# PDU_Sch.net
KiCad netlist of a schematic drawn in Altium Designer
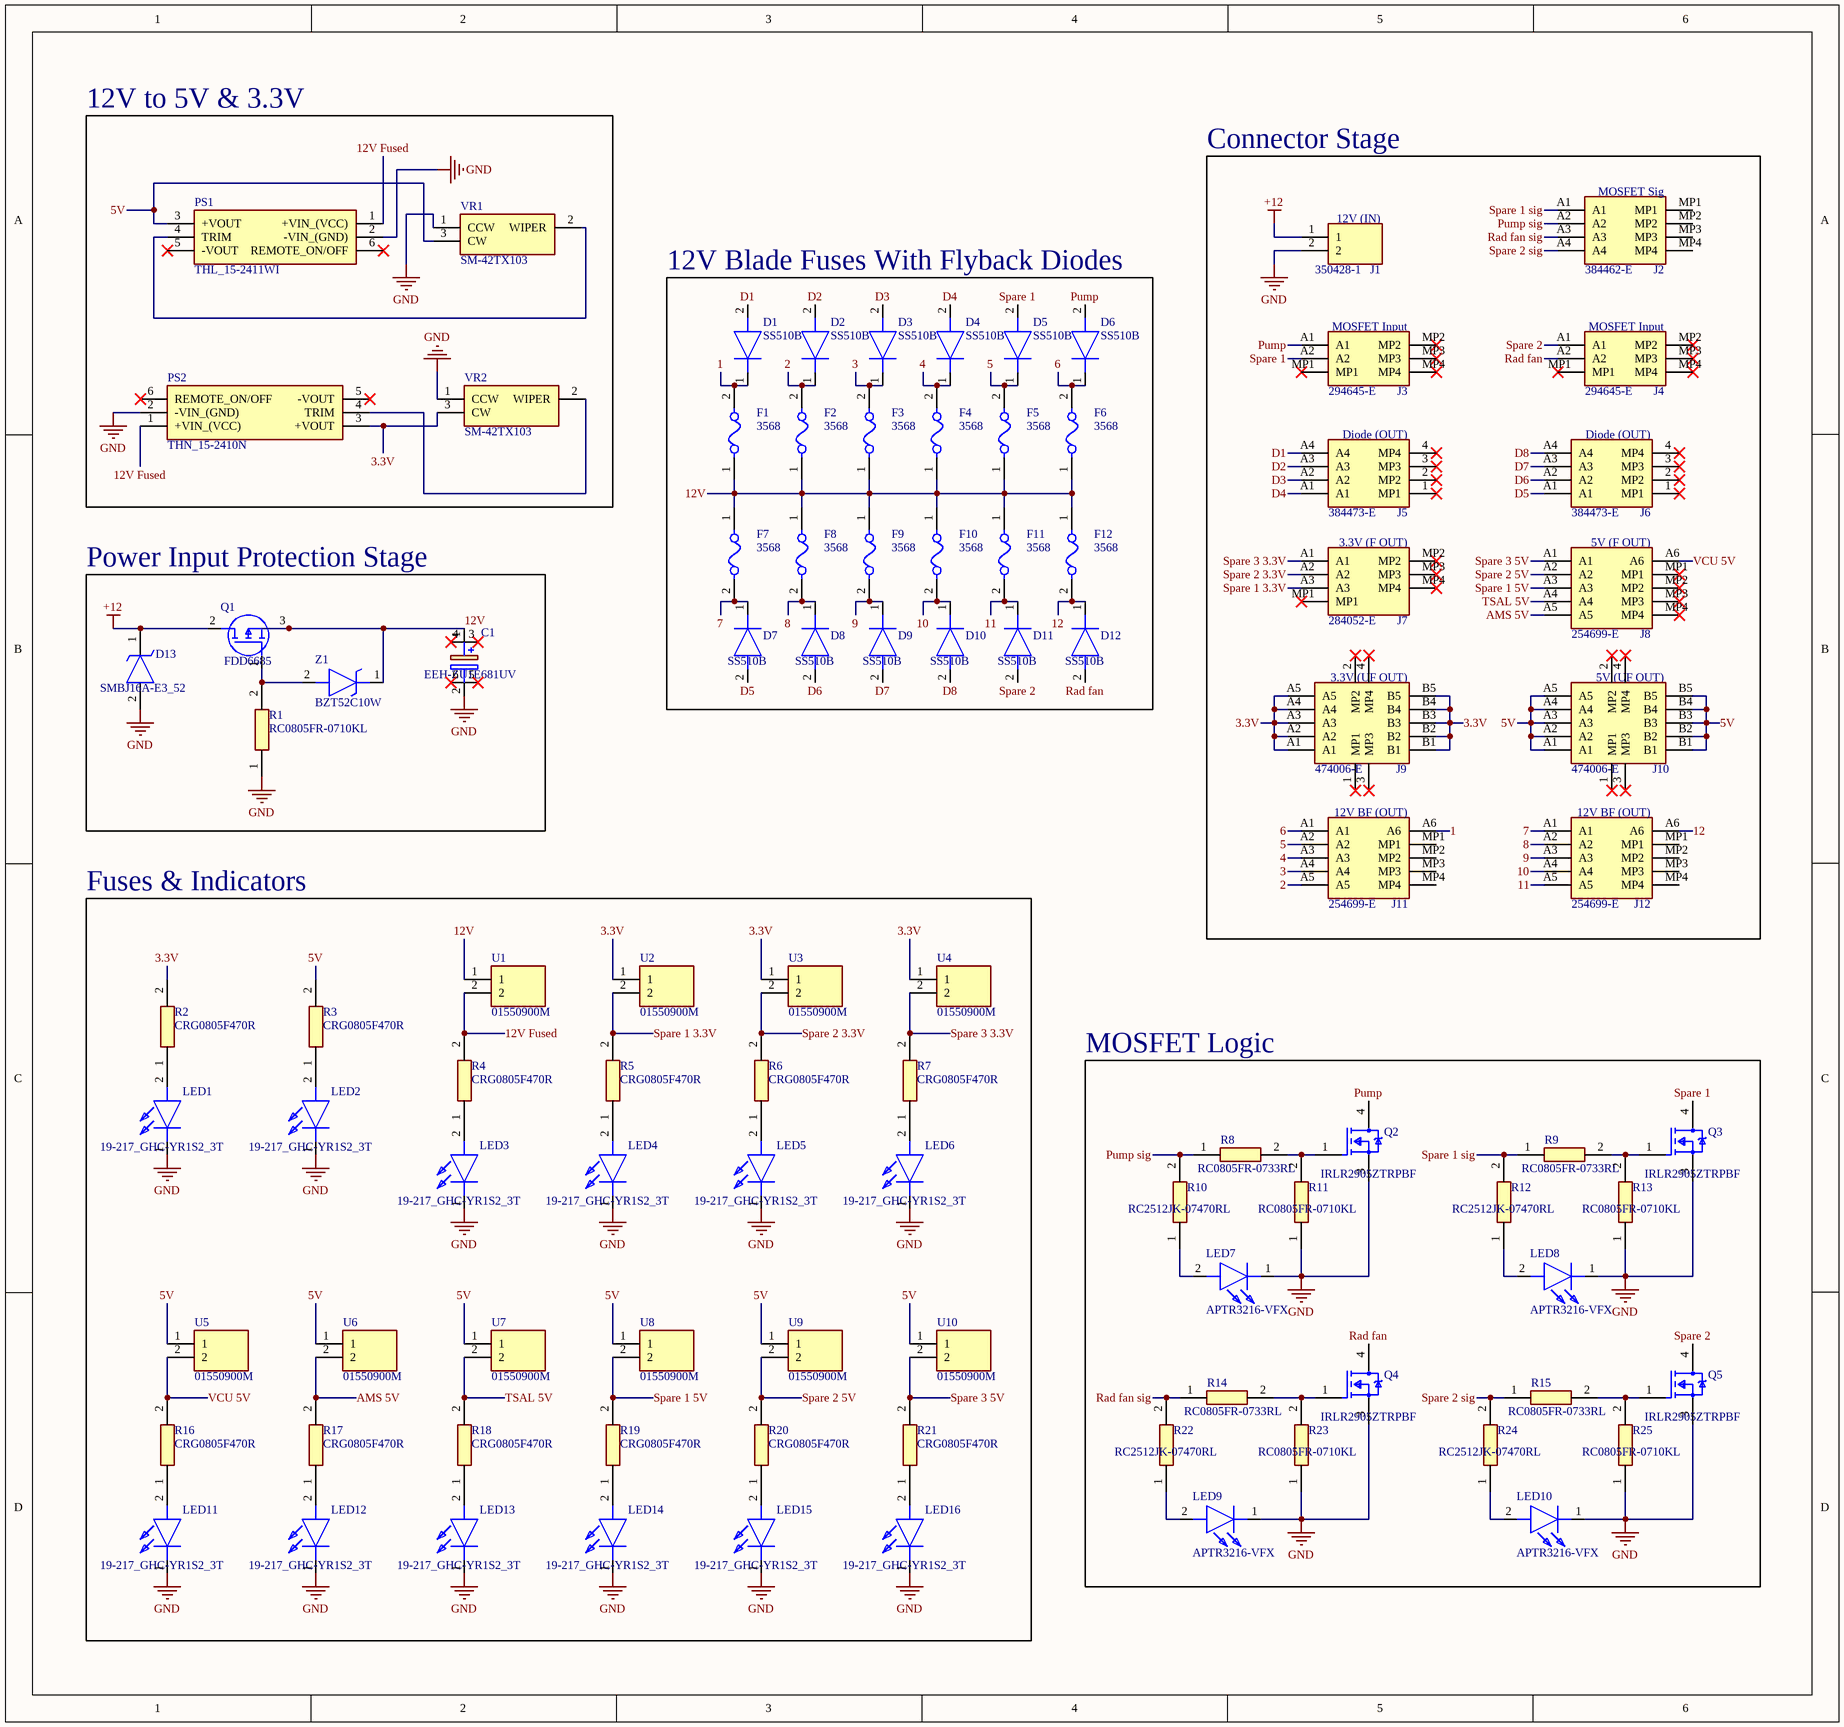
[diagram p0: PDU_Sch.SchDoc]

(export (version "E")
  (design (tool "Eeschema 10.0.6"))
  (components
    (comp (ref "C1")
      (value "EEH-ZU1E681UV")
      (footprint "SamacSys:EEHZU1E681UV")
      (description "Capacitor Polarised (6-Pin Vibration Proof)")
      (fields (field (name "MOUSER PART NUMBER") "667-EEH-ZU1E681UV"))
      (libsource (lib "*") (part "EEH-ZU1E681UV"))
    )
    (comp (ref "D1")
      (value "SS510B")
      (footprint "DIOM5336X244N")
      (description "Diode")
      (libsource (lib "PDU") (part "SS510B"))
    )
    (comp (ref "D2")
      (value "SS510B")
      (footprint "DIOM5336X244N")
      (description "Diode")
      (libsource (lib "PDU") (part "SS510B"))
    )
    (comp (ref "D3")
      (value "SS510B")
      (footprint "DIOM5336X244N")
      (description "Diode")
      (libsource (lib "PDU") (part "SS510B"))
    )
    (comp (ref "D4")
      (value "SS510B")
      (footprint "DIOM5336X244N")
      (description "Diode")
      (libsource (lib "PDU") (part "SS510B"))
    )
    (comp (ref "D5")
      (value "SS510B")
      (footprint "DIOM5336X244N")
      (description "Diode")
      (libsource (lib "PDU") (part "SS510B"))
    )
    (comp (ref "D6")
      (value "SS510B")
      (footprint "DIOM5336X244N")
      (description "Diode")
      (libsource (lib "PDU") (part "SS510B"))
    )
    (comp (ref "D7")
      (value "SS510B")
      (footprint "DIOM5336X244N")
      (description "Diode")
      (libsource (lib "PDU") (part "SS510B"))
    )
    (comp (ref "D8")
      (value "SS510B")
      (footprint "DIOM5336X244N")
      (description "Diode")
      (libsource (lib "PDU") (part "SS510B"))
    )
    (comp (ref "D9")
      (value "SS510B")
      (footprint "DIOM5336X244N")
      (description "Diode")
      (libsource (lib "PDU") (part "SS510B"))
    )
    (comp (ref "D10")
      (value "SS510B")
      (footprint "DIOM5336X244N")
      (description "Diode")
      (libsource (lib "PDU") (part "SS510B"))
    )
    (comp (ref "D11")
      (value "SS510B")
      (footprint "DIOM5336X244N")
      (description "Diode")
      (libsource (lib "PDU") (part "SS510B"))
    )
    (comp (ref "D12")
      (value "SS510B")
      (footprint "DIOM5336X244N")
      (description "Diode")
      (libsource (lib "PDU") (part "SS510B"))
    )
    (comp (ref "D13")
      (value "SMBJ16A-E3_52")
      (footprint "DIOM5436X244N")
      (description "TVS Diode (Uni-directional)")
      (fields
        (field (name "MANUFACTURER_PART_NUMBER") "SMBJ16A-E3/52")
        (field (name "MOUSER PART NUMBER") "625-SMBJ16A-E3")
      )
      (libsource (lib "PDU") (part "SMBJ16A-E3_52"))
    )
    (comp (ref "F1")
      (value "3568")
      (footprint "FP-3568-MFG")
      (fields (field (name "VOLTAGE") "500V"))
      (libsource (lib "Altium Content Vault") (part "3568"))
    )
    (comp (ref "F2")
      (value "3568")
      (footprint "FP-3568-MFG")
      (fields (field (name "VOLTAGE") "500V"))
      (libsource (lib "Altium Content Vault") (part "3568"))
    )
    (comp (ref "F3")
      (value "3568")
      (footprint "FP-3568-MFG")
      (fields (field (name "VOLTAGE") "500V"))
      (libsource (lib "Altium Content Vault") (part "3568"))
    )
    (comp (ref "F4")
      (value "3568")
      (footprint "FP-3568-MFG")
      (fields (field (name "VOLTAGE") "500V"))
      (libsource (lib "Altium Content Vault") (part "3568"))
    )
    (comp (ref "F5")
      (value "3568")
      (footprint "FP-3568-MFG")
      (fields (field (name "VOLTAGE") "500V"))
      (libsource (lib "Altium Content Vault") (part "3568"))
    )
    (comp (ref "F6")
      (value "3568")
      (footprint "FP-3568-MFG")
      (fields (field (name "VOLTAGE") "500V"))
      (libsource (lib "Altium Content Vault") (part "3568"))
    )
    (comp (ref "F7")
      (value "3568")
      (footprint "FP-3568-MFG")
      (fields (field (name "VOLTAGE") "500V"))
      (libsource (lib "Altium Content Vault") (part "3568"))
    )
    (comp (ref "F8")
      (value "3568")
      (footprint "FP-3568-MFG")
      (fields (field (name "VOLTAGE") "500V"))
      (libsource (lib "Altium Content Vault") (part "3568"))
    )
    (comp (ref "F9")
      (value "3568")
      (footprint "FP-3568-MFG")
      (fields (field (name "VOLTAGE") "500V"))
      (libsource (lib "Altium Content Vault") (part "3568"))
    )
    (comp (ref "F10")
      (value "3568")
      (footprint "FP-3568-MFG")
      (fields (field (name "VOLTAGE") "500V"))
      (libsource (lib "Altium Content Vault") (part "3568"))
    )
    (comp (ref "F11")
      (value "3568")
      (footprint "FP-3568-MFG")
      (fields (field (name "VOLTAGE") "500V"))
      (libsource (lib "Altium Content Vault") (part "3568"))
    )
    (comp (ref "F12")
      (value "3568")
      (footprint "FP-3568-MFG")
      (fields (field (name "VOLTAGE") "500V"))
      (libsource (lib "Altium Content Vault") (part "3568"))
    )
    (comp (ref "J1")
      (value "350428-1")
      (footprint "SamacSys:SHDR2W166P0X635_1X2_1397X762X1397P")
      (description "Connector")
      (fields (field (name "MOUSER PART NUMBER") "571-3504281"))
      (libsource (lib "*") (part "350428-1"))
    )
    (comp (ref "J2")
      (value "384462-E")
      (footprint "384462E")
      (description "Connector")
      (fields (field (name "MOUSER PART NUMBER") "305-384462"))
      (libsource (lib "PDU") (part "384462-E"))
    )
    (comp (ref "J3")
      (value "294645-E")
      (footprint "294645E")
      (description "Connector")
      (fields (field (name "MOUSER PART NUMBER") "305-294645"))
      (libsource (lib "PDU") (part "294645-E"))
    )
    (comp (ref "J4")
      (value "294645-E")
      (footprint "294645E")
      (description "Connector")
      (fields (field (name "MOUSER PART NUMBER") "305-294645"))
      (libsource (lib "PDU") (part "294645-E"))
    )
    (comp (ref "J5")
      (value "384473-E")
      (footprint "384473E")
      (description "Connector")
      (libsource (lib "PDU") (part "384473-E"))
    )
    (comp (ref "J6")
      (value "384473-E")
      (footprint "384473E")
      (description "Connector")
      (libsource (lib "PDU") (part "384473-E"))
    )
    (comp (ref "J7")
      (value "284052-E")
      (footprint "284052E")
      (description "Connector")
      (fields (field (name "MOUSER PART NUMBER") "305-284052"))
      (libsource (lib "PDU") (part "284052-E"))
    )
    (comp (ref "J8")
      (value "254699-E")
      (footprint "254699E")
      (description "Connector")
      (fields (field (name "MOUSER PART NUMBER") "305-254699"))
      (libsource (lib "PDU") (part "254699-E"))
    )
    (comp (ref "J9")
      (value "474006-E")
      (footprint "474006E")
      (description "Connector")
      (fields (field (name "MOUSER PART NUMBER") "305-474006"))
      (libsource (lib "PDU") (part "474006-E"))
    )
    (comp (ref "J10")
      (value "474006-E")
      (footprint "474006E")
      (description "Connector")
      (fields (field (name "MOUSER PART NUMBER") "305-474006"))
      (libsource (lib "PDU") (part "474006-E"))
    )
    (comp (ref "J11")
      (value "254699-E")
      (footprint "254699E")
      (description "Connector")
      (fields (field (name "MOUSER PART NUMBER") "305-254699"))
      (libsource (lib "PDU") (part "254699-E"))
    )
    (comp (ref "J12")
      (value "254699-E")
      (footprint "254699E")
      (description "Connector")
      (fields (field (name "MOUSER PART NUMBER") "305-254699"))
      (libsource (lib "PDU") (part "254699-E"))
    )
    (comp (ref "LED1")
      (value "19-217_GHC-YR1S2_3T")
      (footprint "LEDC1608X50N")
      (description "LED")
      (fields
        (field (name "MANUFACTURER_PART_NUMBER") "19-217/GHC-YR1S2/3T")
        (field (name "MOUSER PART NUMBER") "638-19217GHCYR1S23T")
      )
      (libsource (lib "PDU") (part "19-217_GHC-YR1S2_3T"))
    )
    (comp (ref "LED2")
      (value "19-217_GHC-YR1S2_3T")
      (footprint "LEDC1608X50N")
      (description "LED")
      (fields
        (field (name "MANUFACTURER_PART_NUMBER") "19-217/GHC-YR1S2/3T")
        (field (name "MOUSER PART NUMBER") "638-19217GHCYR1S23T")
      )
      (libsource (lib "PDU") (part "19-217_GHC-YR1S2_3T"))
    )
    (comp (ref "LED3")
      (value "19-217_GHC-YR1S2_3T")
      (footprint "LEDC1608X50N")
      (description "LED")
      (fields
        (field (name "MANUFACTURER_PART_NUMBER") "19-217/GHC-YR1S2/3T")
        (field (name "MOUSER PART NUMBER") "638-19217GHCYR1S23T")
      )
      (libsource (lib "PDU") (part "19-217_GHC-YR1S2_3T"))
    )
    (comp (ref "LED4")
      (value "19-217_GHC-YR1S2_3T")
      (footprint "LEDC1608X50N")
      (description "LED")
      (fields
        (field (name "MANUFACTURER_PART_NUMBER") "19-217/GHC-YR1S2/3T")
        (field (name "MOUSER PART NUMBER") "638-19217GHCYR1S23T")
      )
      (libsource (lib "PDU") (part "19-217_GHC-YR1S2_3T"))
    )
    (comp (ref "LED5")
      (value "19-217_GHC-YR1S2_3T")
      (footprint "LEDC1608X50N")
      (description "LED")
      (fields
        (field (name "MANUFACTURER_PART_NUMBER") "19-217/GHC-YR1S2/3T")
        (field (name "MOUSER PART NUMBER") "638-19217GHCYR1S23T")
      )
      (libsource (lib "PDU") (part "19-217_GHC-YR1S2_3T"))
    )
    (comp (ref "LED6")
      (value "19-217_GHC-YR1S2_3T")
      (footprint "LEDC1608X50N")
      (description "LED")
      (fields
        (field (name "MANUFACTURER_PART_NUMBER") "19-217/GHC-YR1S2/3T")
        (field (name "MOUSER PART NUMBER") "638-19217GHCYR1S23T")
      )
      (libsource (lib "PDU") (part "19-217_GHC-YR1S2_3T"))
    )
    (comp (ref "LED7")
      (value "APTR3216-VFX")
      (footprint "LEDC3216X125N")
      (description "LED")
      (fields (field (name "MOUSER PART NUMBER") "604-APTR3216-VFX"))
      (libsource (lib "PDU") (part "APTR3216-VFX"))
    )
    (comp (ref "LED8")
      (value "APTR3216-VFX")
      (footprint "LEDC3216X125N")
      (description "LED")
      (fields (field (name "MOUSER PART NUMBER") "604-APTR3216-VFX"))
      (libsource (lib "PDU") (part "APTR3216-VFX"))
    )
    (comp (ref "LED9")
      (value "APTR3216-VFX")
      (footprint "LEDC3216X125N")
      (description "LED")
      (fields (field (name "MOUSER PART NUMBER") "604-APTR3216-VFX"))
      (libsource (lib "PDU") (part "APTR3216-VFX"))
    )
    (comp (ref "LED10")
      (value "APTR3216-VFX")
      (footprint "LEDC3216X125N")
      (description "LED")
      (fields (field (name "MOUSER PART NUMBER") "604-APTR3216-VFX"))
      (libsource (lib "PDU") (part "APTR3216-VFX"))
    )
    (comp (ref "LED11")
      (value "19-217_GHC-YR1S2_3T")
      (footprint "LEDC1608X50N")
      (description "LED")
      (fields
        (field (name "MANUFACTURER_PART_NUMBER") "19-217/GHC-YR1S2/3T")
        (field (name "MOUSER PART NUMBER") "638-19217GHCYR1S23T")
      )
      (libsource (lib "PDU") (part "19-217_GHC-YR1S2_3T"))
    )
    (comp (ref "LED12")
      (value "19-217_GHC-YR1S2_3T")
      (footprint "LEDC1608X50N")
      (description "LED")
      (fields
        (field (name "MANUFACTURER_PART_NUMBER") "19-217/GHC-YR1S2/3T")
        (field (name "MOUSER PART NUMBER") "638-19217GHCYR1S23T")
      )
      (libsource (lib "PDU") (part "19-217_GHC-YR1S2_3T"))
    )
    (comp (ref "LED13")
      (value "19-217_GHC-YR1S2_3T")
      (footprint "LEDC1608X50N")
      (description "LED")
      (fields
        (field (name "MANUFACTURER_PART_NUMBER") "19-217/GHC-YR1S2/3T")
        (field (name "MOUSER PART NUMBER") "638-19217GHCYR1S23T")
      )
      (libsource (lib "PDU") (part "19-217_GHC-YR1S2_3T"))
    )
    (comp (ref "LED14")
      (value "19-217_GHC-YR1S2_3T")
      (footprint "LEDC1608X50N")
      (description "LED")
      (fields
        (field (name "MANUFACTURER_PART_NUMBER") "19-217/GHC-YR1S2/3T")
        (field (name "MOUSER PART NUMBER") "638-19217GHCYR1S23T")
      )
      (libsource (lib "PDU") (part "19-217_GHC-YR1S2_3T"))
    )
    (comp (ref "LED15")
      (value "19-217_GHC-YR1S2_3T")
      (footprint "LEDC1608X50N")
      (description "LED")
      (fields
        (field (name "MANUFACTURER_PART_NUMBER") "19-217/GHC-YR1S2/3T")
        (field (name "MOUSER PART NUMBER") "638-19217GHCYR1S23T")
      )
      (libsource (lib "PDU") (part "19-217_GHC-YR1S2_3T"))
    )
    (comp (ref "LED16")
      (value "19-217_GHC-YR1S2_3T")
      (footprint "LEDC1608X50N")
      (description "LED")
      (fields
        (field (name "MANUFACTURER_PART_NUMBER") "19-217/GHC-YR1S2/3T")
        (field (name "MOUSER PART NUMBER") "638-19217GHCYR1S23T")
      )
      (libsource (lib "PDU") (part "19-217_GHC-YR1S2_3T"))
    )
    (comp (ref "PS1")
      (value "THL_15-2411WI")
      (footprint "THL152411WI")
      (description "Power Supply")
      (fields
        (field (name "MANUFACTURER_PART_NUMBER") "THL 15-2411WI")
        (field (name "MOUSER PART NUMBER") "495-THL15-2411WI")
      )
      (libsource (lib "PDU") (part "THL_15-2411WI"))
    )
    (comp (ref "PS2")
      (value "THN_15-2410N")
      (footprint "THN152410N")
      (description "Power Supply")
      (fields
        (field (name "MANUFACTURER_PART_NUMBER") "THN 15-2410N")
        (field (name "MOUSER PART NUMBER") "495-THN15-2410N")
      )
      (libsource (lib "PDU") (part "THN_15-2410N"))
    )
    (comp (ref "Q1")
      (value "FDD6685")
      (footprint "FQD1N80TM")
      (description "MOSFET (P-Channel)")
      (fields (field (name "MOUSER PART NUMBER") "512-FDD6685"))
      (libsource (lib "PDU") (part "FDD6685"))
    )
    (comp (ref "Q2")
      (value "IRLR2905ZTRPBF")
      (footprint "FP-PG-TO252-3-MFG")
      (description "MOSFET N-CH 55V 42A DPAK")
      (libsource (lib "Altium Content Vault") (part "1b46a229e508186a6fec6a11ed6f67e"))
    )
    (comp (ref "Q3")
      (value "IRLR2905ZTRPBF")
      (footprint "FP-PG-TO252-3-MFG")
      (description "MOSFET N-CH 55V 42A DPAK")
      (libsource (lib "Altium Content Vault") (part "1b46a229e508186a6fec6a11ed6f67e"))
    )
    (comp (ref "Q4")
      (value "IRLR2905ZTRPBF")
      (footprint "FP-PG-TO252-3-MFG")
      (description "MOSFET N-CH 55V 42A DPAK")
      (libsource (lib "Altium Content Vault") (part "1b46a229e508186a6fec6a11ed6f67e"))
    )
    (comp (ref "Q5")
      (value "IRLR2905ZTRPBF")
      (footprint "FP-PG-TO252-3-MFG")
      (description "MOSFET N-CH 55V 42A DPAK")
      (libsource (lib "Altium Content Vault") (part "1b46a229e508186a6fec6a11ed6f67e"))
    )
    (comp (ref "R1")
      (value "RC0805FR-0710KL")
      (footprint "RESC2012X60N")
      (description "Resistor")
      (fields (field (name "MOUSER PART NUMBER") "603-RC0805FR-0710KL"))
      (libsource (lib "PDU") (part "RC0805FR-0710KL"))
    )
    (comp (ref "R2")
      (value "CRG0805F470R")
      (footprint "RESC2012X65N")
      (description "Resistor")
      (fields (field (name "MOUSER PART NUMBER") "279-CRG0805F470R"))
      (libsource (lib "PDU") (part "CRG0805F470R"))
    )
    (comp (ref "R3")
      (value "CRG0805F470R")
      (footprint "RESC2012X65N")
      (description "Resistor")
      (fields (field (name "MOUSER PART NUMBER") "279-CRG0805F470R"))
      (libsource (lib "PDU") (part "CRG0805F470R"))
    )
    (comp (ref "R4")
      (value "CRG0805F470R")
      (footprint "RESC2012X65N")
      (description "Resistor")
      (fields (field (name "MOUSER PART NUMBER") "279-CRG0805F470R"))
      (libsource (lib "PDU") (part "CRG0805F470R"))
    )
    (comp (ref "R5")
      (value "CRG0805F470R")
      (footprint "RESC2012X65N")
      (description "Resistor")
      (fields (field (name "MOUSER PART NUMBER") "279-CRG0805F470R"))
      (libsource (lib "PDU") (part "CRG0805F470R"))
    )
    (comp (ref "R6")
      (value "CRG0805F470R")
      (footprint "RESC2012X65N")
      (description "Resistor")
      (fields (field (name "MOUSER PART NUMBER") "279-CRG0805F470R"))
      (libsource (lib "PDU") (part "CRG0805F470R"))
    )
    (comp (ref "R7")
      (value "CRG0805F470R")
      (footprint "RESC2012X65N")
      (description "Resistor")
      (fields (field (name "MOUSER PART NUMBER") "279-CRG0805F470R"))
      (libsource (lib "PDU") (part "CRG0805F470R"))
    )
    (comp (ref "R8")
      (value "RC0805FR-0733RL")
      (footprint "RESC2012X60N")
      (description "Resistor")
      (fields (field (name "MOUSER PART NUMBER") "603-RC0805FR-0733RL"))
      (libsource (lib "PDU") (part "RC0805FR-0733RL"))
    )
    (comp (ref "R9")
      (value "RC0805FR-0733RL")
      (footprint "RESC2012X60N")
      (description "Resistor")
      (fields (field (name "MOUSER PART NUMBER") "603-RC0805FR-0733RL"))
      (libsource (lib "PDU") (part "RC0805FR-0733RL"))
    )
    (comp (ref "R10")
      (value "RC2512JK-07470RL")
      (footprint "RESC6431X65N")
      (description "Resistor")
      (fields (field (name "MOUSER PART NUMBER") "603-RC2512JK-07470RL"))
      (libsource (lib "PDU") (part "RC2512JK-07470RL"))
    )
    (comp (ref "R11")
      (value "RC0805FR-0710KL")
      (footprint "RESC2012X60N")
      (description "Resistor")
      (fields (field (name "MOUSER PART NUMBER") "603-RC0805FR-0710KL"))
      (libsource (lib "PDU") (part "RC0805FR-0710KL"))
    )
    (comp (ref "R12")
      (value "RC2512JK-07470RL")
      (footprint "RESC6431X65N")
      (description "Resistor")
      (fields (field (name "MOUSER PART NUMBER") "603-RC2512JK-07470RL"))
      (libsource (lib "PDU") (part "RC2512JK-07470RL"))
    )
    (comp (ref "R13")
      (value "RC0805FR-0710KL")
      (footprint "RESC2012X60N")
      (description "Resistor")
      (fields (field (name "MOUSER PART NUMBER") "603-RC0805FR-0710KL"))
      (libsource (lib "PDU") (part "RC0805FR-0710KL"))
    )
    (comp (ref "R14")
      (value "RC0805FR-0733RL")
      (footprint "RESC2012X60N")
      (description "Resistor")
      (fields (field (name "MOUSER PART NUMBER") "603-RC0805FR-0733RL"))
      (libsource (lib "PDU") (part "RC0805FR-0733RL"))
    )
    (comp (ref "R15")
      (value "RC0805FR-0733RL")
      (footprint "RESC2012X60N")
      (description "Resistor")
      (fields (field (name "MOUSER PART NUMBER") "603-RC0805FR-0733RL"))
      (libsource (lib "PDU") (part "RC0805FR-0733RL"))
    )
    (comp (ref "R16")
      (value "CRG0805F470R")
      (footprint "RESC2012X65N")
      (description "Resistor")
      (fields (field (name "MOUSER PART NUMBER") "279-CRG0805F470R"))
      (libsource (lib "PDU") (part "CRG0805F470R"))
    )
    (comp (ref "R17")
      (value "CRG0805F470R")
      (footprint "RESC2012X65N")
      (description "Resistor")
      (fields (field (name "MOUSER PART NUMBER") "279-CRG0805F470R"))
      (libsource (lib "PDU") (part "CRG0805F470R"))
    )
    (comp (ref "R18")
      (value "CRG0805F470R")
      (footprint "RESC2012X65N")
      (description "Resistor")
      (fields (field (name "MOUSER PART NUMBER") "279-CRG0805F470R"))
      (libsource (lib "PDU") (part "CRG0805F470R"))
    )
    (comp (ref "R19")
      (value "CRG0805F470R")
      (footprint "RESC2012X65N")
      (description "Resistor")
      (fields (field (name "MOUSER PART NUMBER") "279-CRG0805F470R"))
      (libsource (lib "PDU") (part "CRG0805F470R"))
    )
    (comp (ref "R20")
      (value "CRG0805F470R")
      (footprint "RESC2012X65N")
      (description "Resistor")
      (fields (field (name "MOUSER PART NUMBER") "279-CRG0805F470R"))
      (libsource (lib "PDU") (part "CRG0805F470R"))
    )
    (comp (ref "R21")
      (value "CRG0805F470R")
      (footprint "RESC2012X65N")
      (description "Resistor")
      (fields (field (name "MOUSER PART NUMBER") "279-CRG0805F470R"))
      (libsource (lib "PDU") (part "CRG0805F470R"))
    )
    (comp (ref "R22")
      (value "RC2512JK-07470RL")
      (footprint "RESC6431X65N")
      (description "Resistor")
      (fields (field (name "MOUSER PART NUMBER") "603-RC2512JK-07470RL"))
      (libsource (lib "PDU") (part "RC2512JK-07470RL"))
    )
    (comp (ref "R23")
      (value "RC0805FR-0710KL")
      (footprint "RESC2012X60N")
      (description "Resistor")
      (fields (field (name "MOUSER PART NUMBER") "603-RC0805FR-0710KL"))
      (libsource (lib "PDU") (part "RC0805FR-0710KL"))
    )
    (comp (ref "R24")
      (value "RC2512JK-07470RL")
      (footprint "RESC6431X65N")
      (description "Resistor")
      (fields (field (name "MOUSER PART NUMBER") "603-RC2512JK-07470RL"))
      (libsource (lib "PDU") (part "RC2512JK-07470RL"))
    )
    (comp (ref "R25")
      (value "RC0805FR-0710KL")
      (footprint "RESC2012X60N")
      (description "Resistor")
      (fields (field (name "MOUSER PART NUMBER") "603-RC0805FR-0710KL"))
      (libsource (lib "PDU") (part "RC0805FR-0710KL"))
    )
    (comp (ref "U1")
      (value "01550900M")
      (footprint "01550900M")
      (description "Undefined or Miscellaneous")
      (fields (field (name "MOUSER PART NUMBER") "576-01550900M"))
      (libsource (lib "PDU") (part "01550900M"))
    )
    (comp (ref "U2")
      (value "01550900M")
      (footprint "01550900M")
      (description "Undefined or Miscellaneous")
      (fields (field (name "MOUSER PART NUMBER") "576-01550900M"))
      (libsource (lib "PDU") (part "01550900M"))
    )
    (comp (ref "U3")
      (value "01550900M")
      (footprint "01550900M")
      (description "Undefined or Miscellaneous")
      (fields (field (name "MOUSER PART NUMBER") "576-01550900M"))
      (libsource (lib "PDU") (part "01550900M"))
    )
    (comp (ref "U4")
      (value "01550900M")
      (footprint "01550900M")
      (description "Undefined or Miscellaneous")
      (fields (field (name "MOUSER PART NUMBER") "576-01550900M"))
      (libsource (lib "PDU") (part "01550900M"))
    )
    (comp (ref "U5")
      (value "01550900M")
      (footprint "01550900M")
      (description "Undefined or Miscellaneous")
      (fields (field (name "MOUSER PART NUMBER") "576-01550900M"))
      (libsource (lib "PDU") (part "01550900M"))
    )
    (comp (ref "U6")
      (value "01550900M")
      (footprint "01550900M")
      (description "Undefined or Miscellaneous")
      (fields (field (name "MOUSER PART NUMBER") "576-01550900M"))
      (libsource (lib "PDU") (part "01550900M"))
    )
    (comp (ref "U7")
      (value "01550900M")
      (footprint "01550900M")
      (description "Undefined or Miscellaneous")
      (fields (field (name "MOUSER PART NUMBER") "576-01550900M"))
      (libsource (lib "PDU") (part "01550900M"))
    )
    (comp (ref "U8")
      (value "01550900M")
      (footprint "01550900M")
      (description "Undefined or Miscellaneous")
      (fields (field (name "MOUSER PART NUMBER") "576-01550900M"))
      (libsource (lib "PDU") (part "01550900M"))
    )
    (comp (ref "U9")
      (value "01550900M")
      (footprint "01550900M")
      (description "Undefined or Miscellaneous")
      (fields (field (name "MOUSER PART NUMBER") "576-01550900M"))
      (libsource (lib "PDU") (part "01550900M"))
    )
    (comp (ref "U10")
      (value "01550900M")
      (footprint "01550900M")
      (description "Undefined or Miscellaneous")
      (fields (field (name "MOUSER PART NUMBER") "576-01550900M"))
      (libsource (lib "PDU") (part "01550900M"))
    )
    (comp (ref "VR1")
      (value "SM-42TX103")
      (footprint "SM42TX103")
      (description "Variable Resistor")
      (fields (field (name "MOUSER PART NUMBER") "229-SM-42TX103"))
      (libsource (lib "PDU") (part "SM-42TX103"))
    )
    (comp (ref "VR2")
      (value "SM-42TX103")
      (footprint "SM42TX103")
      (description "Variable Resistor")
      (fields (field (name "MOUSER PART NUMBER") "229-SM-42TX103"))
      (libsource (lib "PDU") (part "SM-42TX103"))
    )
    (comp (ref "Z1")
      (value "BZT52C10W")
      (footprint "BZT52C10W")
      (description "Zener Diode")
      (libsource (lib "PDU") (part "BZT52C10W"))
    )
  )
  (nets
    (net (code "1") (name "+12") (class "Default")
      (node (ref "D13") (pin "1") (pinfunction "K_1") (pintype "passive"))
      (node (ref "J1") (pin "1") (pinfunction "1_1") (pintype "passive"))
      (node (ref "Q1") (pin "2") (pinfunction "D_2") (pintype "passive"))
    )
    (net (code "2") (name "/1") (class "Default")
      (node (ref "D1") (pin "1") (pinfunction "K_1") (pintype "passive"))
      (node (ref "F1") (pin "2") (pinfunction "2_2") (pintype "passive"))
      (node (ref "J11") (pin "A6") (pinfunction "A6_A6") (pintype "passive"))
    )
    (net (code "3") (name "/2") (class "Default")
      (node (ref "D2") (pin "1") (pinfunction "K_1") (pintype "passive"))
      (node (ref "F2") (pin "2") (pinfunction "2_2") (pintype "passive"))
      (node (ref "J11") (pin "A5") (pinfunction "A5_A5") (pintype "passive"))
    )
    (net (code "4") (name "/3") (class "Default")
      (node (ref "D3") (pin "1") (pinfunction "K_1") (pintype "passive"))
      (node (ref "F3") (pin "2") (pinfunction "2_2") (pintype "passive"))
      (node (ref "J11") (pin "A4") (pinfunction "A4_A4") (pintype "passive"))
    )
    (net (code "5") (name "/3.3V") (class "Default")
      (node (ref "J9") (pin "A1") (pinfunction "A1_A1") (pintype "passive"))
      (node (ref "J9") (pin "A2") (pinfunction "A2_A2") (pintype "passive"))
      (node (ref "J9") (pin "A3") (pinfunction "A3_A3") (pintype "passive"))
      (node (ref "J9") (pin "A4") (pinfunction "A4_A4") (pintype "passive"))
      (node (ref "J9") (pin "A5") (pinfunction "A5_A5") (pintype "passive"))
      (node (ref "J9") (pin "B1") (pinfunction "B1_B1") (pintype "passive"))
      (node (ref "J9") (pin "B2") (pinfunction "B2_B2") (pintype "passive"))
      (node (ref "J9") (pin "B3") (pinfunction "B3_B3") (pintype "passive"))
      (node (ref "J9") (pin "B4") (pinfunction "B4_B4") (pintype "passive"))
      (node (ref "J9") (pin "B5") (pinfunction "B5_B5") (pintype "passive"))
      (node (ref "PS2") (pin "3") (pinfunction "+VOUT_3") (pintype "passive"))
      (node (ref "R2") (pin "2") (pinfunction "2_2") (pintype "passive"))
      (node (ref "U2") (pin "1") (pinfunction "1_1") (pintype "passive"))
      (node (ref "U3") (pin "1") (pinfunction "1_1") (pintype "passive"))
      (node (ref "U4") (pin "1") (pinfunction "1_1") (pintype "passive"))
      (node (ref "VR2") (pin "3") (pinfunction "CW_3") (pintype "passive"))
    )
    (net (code "6") (name "/4") (class "Default")
      (node (ref "D4") (pin "1") (pinfunction "K_1") (pintype "passive"))
      (node (ref "F4") (pin "2") (pinfunction "2_2") (pintype "passive"))
      (node (ref "J11") (pin "A3") (pinfunction "A3_A3") (pintype "passive"))
    )
    (net (code "7") (name "/5") (class "Default")
      (node (ref "D5") (pin "1") (pinfunction "K_1") (pintype "passive"))
      (node (ref "F5") (pin "2") (pinfunction "2_2") (pintype "passive"))
      (node (ref "J11") (pin "A2") (pinfunction "A2_A2") (pintype "passive"))
    )
    (net (code "8") (name "/5V") (class "Default")
      (node (ref "J10") (pin "A1") (pinfunction "A1_A1") (pintype "passive"))
      (node (ref "J10") (pin "A2") (pinfunction "A2_A2") (pintype "passive"))
      (node (ref "J10") (pin "A3") (pinfunction "A3_A3") (pintype "passive"))
      (node (ref "J10") (pin "A4") (pinfunction "A4_A4") (pintype "passive"))
      (node (ref "J10") (pin "A5") (pinfunction "A5_A5") (pintype "passive"))
      (node (ref "J10") (pin "B1") (pinfunction "B1_B1") (pintype "passive"))
      (node (ref "J10") (pin "B2") (pinfunction "B2_B2") (pintype "passive"))
      (node (ref "J10") (pin "B3") (pinfunction "B3_B3") (pintype "passive"))
      (node (ref "J10") (pin "B4") (pinfunction "B4_B4") (pintype "passive"))
      (node (ref "J10") (pin "B5") (pinfunction "B5_B5") (pintype "passive"))
      (node (ref "PS1") (pin "3") (pinfunction "+VOUT_3") (pintype "passive"))
      (node (ref "R3") (pin "2") (pinfunction "2_2") (pintype "passive"))
      (node (ref "U10") (pin "1") (pinfunction "1_1") (pintype "passive"))
      (node (ref "U5") (pin "1") (pinfunction "1_1") (pintype "passive"))
      (node (ref "U6") (pin "1") (pinfunction "1_1") (pintype "passive"))
      (node (ref "U7") (pin "1") (pinfunction "1_1") (pintype "passive"))
      (node (ref "U8") (pin "1") (pinfunction "1_1") (pintype "passive"))
      (node (ref "U9") (pin "1") (pinfunction "1_1") (pintype "passive"))
      (node (ref "VR1") (pin "3") (pinfunction "CW_3") (pintype "passive"))
    )
    (net (code "9") (name "/6") (class "Default")
      (node (ref "D6") (pin "1") (pinfunction "K_1") (pintype "passive"))
      (node (ref "F6") (pin "2") (pinfunction "2_2") (pintype "passive"))
      (node (ref "J11") (pin "A1") (pinfunction "A1_A1") (pintype "passive"))
    )
    (net (code "10") (name "/7") (class "Default")
      (node (ref "D7") (pin "1") (pinfunction "K_1") (pintype "passive"))
      (node (ref "F7") (pin "2") (pinfunction "2_2") (pintype "passive"))
      (node (ref "J12") (pin "A1") (pinfunction "A1_A1") (pintype "passive"))
    )
    (net (code "11") (name "/8") (class "Default")
      (node (ref "D8") (pin "1") (pinfunction "K_1") (pintype "passive"))
      (node (ref "F8") (pin "2") (pinfunction "2_2") (pintype "passive"))
      (node (ref "J12") (pin "A2") (pinfunction "A2_A2") (pintype "passive"))
    )
    (net (code "12") (name "/9") (class "Default")
      (node (ref "D9") (pin "1") (pinfunction "K_1") (pintype "passive"))
      (node (ref "F9") (pin "2") (pinfunction "2_2") (pintype "passive"))
      (node (ref "J12") (pin "A3") (pinfunction "A3_A3") (pintype "passive"))
    )
    (net (code "13") (name "/10") (class "Default")
      (node (ref "D10") (pin "1") (pinfunction "K_1") (pintype "passive"))
      (node (ref "F10") (pin "2") (pinfunction "2_2") (pintype "passive"))
      (node (ref "J12") (pin "A4") (pinfunction "A4_A4") (pintype "passive"))
    )
    (net (code "14") (name "/11") (class "Default")
      (node (ref "D11") (pin "1") (pinfunction "K_1") (pintype "passive"))
      (node (ref "F11") (pin "2") (pinfunction "2_2") (pintype "passive"))
      (node (ref "J12") (pin "A5") (pinfunction "A5_A5") (pintype "passive"))
    )
    (net (code "15") (name "/12") (class "Default")
      (node (ref "D12") (pin "1") (pinfunction "K_1") (pintype "passive"))
      (node (ref "F12") (pin "2") (pinfunction "2_2") (pintype "passive"))
      (node (ref "J12") (pin "A6") (pinfunction "A6_A6") (pintype "passive"))
    )
    (net (code "16") (name "/12V") (class "Default")
      (node (ref "C1") (pin "1") (pinfunction "+_1_1") (pintype "passive"))
      (node (ref "F1") (pin "1") (pinfunction "1_1") (pintype "passive"))
      (node (ref "F10") (pin "1") (pinfunction "1_1") (pintype "passive"))
      (node (ref "F11") (pin "1") (pinfunction "1_1") (pintype "passive"))
      (node (ref "F12") (pin "1") (pinfunction "1_1") (pintype "passive"))
      (node (ref "F2") (pin "1") (pinfunction "1_1") (pintype "passive"))
      (node (ref "F3") (pin "1") (pinfunction "1_1") (pintype "passive"))
      (node (ref "F4") (pin "1") (pinfunction "1_1") (pintype "passive"))
      (node (ref "F5") (pin "1") (pinfunction "1_1") (pintype "passive"))
      (node (ref "F6") (pin "1") (pinfunction "1_1") (pintype "passive"))
      (node (ref "F7") (pin "1") (pinfunction "1_1") (pintype "passive"))
      (node (ref "F8") (pin "1") (pinfunction "1_1") (pintype "passive"))
      (node (ref "F9") (pin "1") (pinfunction "1_1") (pintype "passive"))
      (node (ref "Q1") (pin "3") (pinfunction "S_3") (pintype "passive"))
      (node (ref "U1") (pin "1") (pinfunction "1_1") (pintype "passive"))
      (node (ref "Z1") (pin "1") (pinfunction "K_1") (pintype "passive"))
    )
    (net (code "17") (name "/12V Fused") (class "Default")
      (node (ref "PS1") (pin "1") (pinfunction "+VIN_(VCC)_1") (pintype "passive"))
      (node (ref "PS2") (pin "1") (pinfunction "+VIN_(VCC)_1") (pintype "passive"))
      (node (ref "R4") (pin "2") (pinfunction "2_2") (pintype "passive"))
      (node (ref "U1") (pin "2") (pinfunction "2_2") (pintype "passive"))
    )
    (net (code "18") (name "/AMS 5V") (class "Default")
      (node (ref "J8") (pin "A5") (pinfunction "A5_A5") (pintype "passive"))
      (node (ref "R17") (pin "2") (pinfunction "2_2") (pintype "passive"))
      (node (ref "U6") (pin "2") (pinfunction "2_2") (pintype "passive"))
    )
    (net (code "19") (name "/D1") (class "Default")
      (node (ref "D1") (pin "2") (pinfunction "A_2") (pintype "passive"))
      (node (ref "J5") (pin "A4") (pinfunction "A4_A4") (pintype "passive"))
    )
    (net (code "20") (name "/D2") (class "Default")
      (node (ref "D2") (pin "2") (pinfunction "A_2") (pintype "passive"))
      (node (ref "J5") (pin "A3") (pinfunction "A3_A3") (pintype "passive"))
    )
    (net (code "21") (name "/D3") (class "Default")
      (node (ref "D3") (pin "2") (pinfunction "A_2") (pintype "passive"))
      (node (ref "J5") (pin "A2") (pinfunction "A2_A2") (pintype "passive"))
    )
    (net (code "22") (name "/D4") (class "Default")
      (node (ref "D4") (pin "2") (pinfunction "A_2") (pintype "passive"))
      (node (ref "J5") (pin "A1") (pinfunction "A1_A1") (pintype "passive"))
    )
    (net (code "23") (name "/D5") (class "Default")
      (node (ref "D7") (pin "2") (pinfunction "A_2") (pintype "passive"))
      (node (ref "J6") (pin "A1") (pinfunction "A1_A1") (pintype "passive"))
    )
    (net (code "24") (name "/D6") (class "Default")
      (node (ref "D8") (pin "2") (pinfunction "A_2") (pintype "passive"))
      (node (ref "J6") (pin "A2") (pinfunction "A2_A2") (pintype "passive"))
    )
    (net (code "25") (name "/D7") (class "Default")
      (node (ref "D9") (pin "2") (pinfunction "A_2") (pintype "passive"))
      (node (ref "J6") (pin "A3") (pinfunction "A3_A3") (pintype "passive"))
    )
    (net (code "26") (name "/D8") (class "Default")
      (node (ref "D10") (pin "2") (pinfunction "A_2") (pintype "passive"))
      (node (ref "J6") (pin "A4") (pinfunction "A4_A4") (pintype "passive"))
    )
    (net (code "27") (name "/Pump") (class "Default")
      (node (ref "D6") (pin "2") (pinfunction "A_2") (pintype "passive"))
      (node (ref "J3") (pin "A1") (pinfunction "A1_A1") (pintype "passive"))
      (node (ref "Q2") (pin "4") (pinfunction "D_4") (pintype "passive"))
    )
    (net (code "28") (name "/Pump sig") (class "Default")
      (node (ref "J2") (pin "A2") (pinfunction "A2_A2") (pintype "passive"))
      (node (ref "R10") (pin "2") (pinfunction "2_2") (pintype "passive"))
      (node (ref "R8") (pin "1") (pinfunction "1_1") (pintype "passive"))
    )
    (net (code "29") (name "/Rad fan") (class "Default")
      (node (ref "D12") (pin "2") (pinfunction "A_2") (pintype "passive"))
      (node (ref "J4") (pin "A2") (pinfunction "A2_A2") (pintype "passive"))
      (node (ref "Q4") (pin "4") (pinfunction "D_4") (pintype "passive"))
    )
    (net (code "30") (name "/Rad fan sig") (class "Default")
      (node (ref "J2") (pin "A3") (pinfunction "A3_A3") (pintype "passive"))
      (node (ref "R14") (pin "1") (pinfunction "1_1") (pintype "passive"))
      (node (ref "R22") (pin "2") (pinfunction "2_2") (pintype "passive"))
    )
    (net (code "31") (name "/Spare 1") (class "Default")
      (node (ref "D5") (pin "2") (pinfunction "A_2") (pintype "passive"))
      (node (ref "J3") (pin "A2") (pinfunction "A2_A2") (pintype "passive"))
      (node (ref "Q3") (pin "4") (pinfunction "D_4") (pintype "passive"))
    )
    (net (code "32") (name "/Spare 1 3.3V") (class "Default")
      (node (ref "J7") (pin "A3") (pinfunction "A3_A3") (pintype "passive"))
      (node (ref "R5") (pin "2") (pinfunction "2_2") (pintype "passive"))
      (node (ref "U2") (pin "2") (pinfunction "2_2") (pintype "passive"))
    )
    (net (code "33") (name "/Spare 1 5V") (class "Default")
      (node (ref "J8") (pin "A3") (pinfunction "A3_A3") (pintype "passive"))
      (node (ref "R19") (pin "2") (pinfunction "2_2") (pintype "passive"))
      (node (ref "U8") (pin "2") (pinfunction "2_2") (pintype "passive"))
    )
    (net (code "34") (name "/Spare 1 sig") (class "Default")
      (node (ref "J2") (pin "A1") (pinfunction "A1_A1") (pintype "passive"))
      (node (ref "R12") (pin "2") (pinfunction "2_2") (pintype "passive"))
      (node (ref "R9") (pin "1") (pinfunction "1_1") (pintype "passive"))
    )
    (net (code "35") (name "/Spare 2") (class "Default")
      (node (ref "D11") (pin "2") (pinfunction "A_2") (pintype "passive"))
      (node (ref "J4") (pin "A1") (pinfunction "A1_A1") (pintype "passive"))
      (node (ref "Q5") (pin "4") (pinfunction "D_4") (pintype "passive"))
    )
    (net (code "36") (name "/Spare 2 3.3V") (class "Default")
      (node (ref "J7") (pin "A2") (pinfunction "A2_A2") (pintype "passive"))
      (node (ref "R6") (pin "2") (pinfunction "2_2") (pintype "passive"))
      (node (ref "U3") (pin "2") (pinfunction "2_2") (pintype "passive"))
    )
    (net (code "37") (name "/Spare 2 5V") (class "Default")
      (node (ref "J8") (pin "A2") (pinfunction "A2_A2") (pintype "passive"))
      (node (ref "R20") (pin "2") (pinfunction "2_2") (pintype "passive"))
      (node (ref "U9") (pin "2") (pinfunction "2_2") (pintype "passive"))
    )
    (net (code "38") (name "/Spare 2 sig") (class "Default")
      (node (ref "J2") (pin "A4") (pinfunction "A4_A4") (pintype "passive"))
      (node (ref "R15") (pin "1") (pinfunction "1_1") (pintype "passive"))
      (node (ref "R24") (pin "2") (pinfunction "2_2") (pintype "passive"))
    )
    (net (code "39") (name "/Spare 3 3.3V") (class "Default")
      (node (ref "J7") (pin "A1") (pinfunction "A1_A1") (pintype "passive"))
      (node (ref "R7") (pin "2") (pinfunction "2_2") (pintype "passive"))
      (node (ref "U4") (pin "2") (pinfunction "2_2") (pintype "passive"))
    )
    (net (code "40") (name "/Spare 3 5V") (class "Default")
      (node (ref "J8") (pin "A1") (pinfunction "A1_A1") (pintype "passive"))
      (node (ref "R21") (pin "2") (pinfunction "2_2") (pintype "passive"))
      (node (ref "U10") (pin "2") (pinfunction "2_2") (pintype "passive"))
    )
    (net (code "41") (name "/TSAL 5V") (class "Default")
      (node (ref "J8") (pin "A4") (pinfunction "A4_A4") (pintype "passive"))
      (node (ref "R18") (pin "2") (pinfunction "2_2") (pintype "passive"))
      (node (ref "U7") (pin "2") (pinfunction "2_2") (pintype "passive"))
    )
    (net (code "42") (name "/VCU 5V") (class "Default")
      (node (ref "J8") (pin "A6") (pinfunction "A6_A6") (pintype "passive"))
      (node (ref "R16") (pin "2") (pinfunction "2_2") (pintype "passive"))
      (node (ref "U5") (pin "2") (pinfunction "2_2") (pintype "passive"))
    )
    (net (code "43") (name "GND") (class "Default")
      (node (ref "C1") (pin "2") (pinfunction "-_1_2") (pintype "passive"))
      (node (ref "D13") (pin "2") (pinfunction "A_2") (pintype "passive"))
      (node (ref "J1") (pin "2") (pinfunction "2_2") (pintype "passive"))
      (node (ref "LED1") (pin "1") (pinfunction "K_1") (pintype "passive"))
      (node (ref "LED10") (pin "1") (pinfunction "K_1") (pintype "passive"))
      (node (ref "LED11") (pin "1") (pinfunction "K_1") (pintype "passive"))
      (node (ref "LED12") (pin "1") (pinfunction "K_1") (pintype "passive"))
      (node (ref "LED13") (pin "1") (pinfunction "K_1") (pintype "passive"))
      (node (ref "LED14") (pin "1") (pinfunction "K_1") (pintype "passive"))
      (node (ref "LED15") (pin "1") (pinfunction "K_1") (pintype "passive"))
      (node (ref "LED16") (pin "1") (pinfunction "K_1") (pintype "passive"))
      (node (ref "LED2") (pin "1") (pinfunction "K_1") (pintype "passive"))
      (node (ref "LED3") (pin "1") (pinfunction "K_1") (pintype "passive"))
      (node (ref "LED4") (pin "1") (pinfunction "K_1") (pintype "passive"))
      (node (ref "LED5") (pin "1") (pinfunction "K_1") (pintype "passive"))
      (node (ref "LED6") (pin "1") (pinfunction "K_1") (pintype "passive"))
      (node (ref "LED7") (pin "1") (pinfunction "K_1") (pintype "passive"))
      (node (ref "LED8") (pin "1") (pinfunction "K_1") (pintype "passive"))
      (node (ref "LED9") (pin "1") (pinfunction "K_1") (pintype "passive"))
      (node (ref "PS1") (pin "2") (pinfunction "-VIN_(GND)_2") (pintype "passive"))
      (node (ref "PS2") (pin "2") (pinfunction "-VIN_(GND)_2") (pintype "passive"))
      (node (ref "Q2") (pin "3") (pinfunction "S_3") (pintype "passive"))
      (node (ref "Q3") (pin "3") (pinfunction "S_3") (pintype "passive"))
      (node (ref "Q4") (pin "3") (pinfunction "S_3") (pintype "passive"))
      (node (ref "Q5") (pin "3") (pinfunction "S_3") (pintype "passive"))
      (node (ref "R1") (pin "1") (pinfunction "1_1") (pintype "passive"))
      (node (ref "R11") (pin "1") (pinfunction "1_1") (pintype "passive"))
      (node (ref "R13") (pin "1") (pinfunction "1_1") (pintype "passive"))
      (node (ref "R23") (pin "1") (pinfunction "1_1") (pintype "passive"))
      (node (ref "R25") (pin "1") (pinfunction "1_1") (pintype "passive"))
      (node (ref "VR1") (pin "1") (pinfunction "CCW_1") (pintype "passive"))
      (node (ref "VR2") (pin "1") (pinfunction "CCW_1") (pintype "passive"))
    )
    (net (code "44") (name "Net-(LED1-A)") (class "Default")
      (node (ref "LED1") (pin "2") (pinfunction "A_2") (pintype "passive"))
      (node (ref "R2") (pin "1") (pinfunction "1_1") (pintype "passive"))
    )
    (net (code "45") (name "Net-(LED2-A)") (class "Default")
      (node (ref "LED2") (pin "2") (pinfunction "A_2") (pintype "passive"))
      (node (ref "R3") (pin "1") (pinfunction "1_1") (pintype "passive"))
    )
    (net (code "46") (name "Net-(LED3-A)") (class "Default")
      (node (ref "LED3") (pin "2") (pinfunction "A_2") (pintype "passive"))
      (node (ref "R4") (pin "1") (pinfunction "1_1") (pintype "passive"))
    )
    (net (code "47") (name "Net-(LED4-A)") (class "Default")
      (node (ref "LED4") (pin "2") (pinfunction "A_2") (pintype "passive"))
      (node (ref "R5") (pin "1") (pinfunction "1_1") (pintype "passive"))
    )
    (net (code "48") (name "Net-(LED5-A)") (class "Default")
      (node (ref "LED5") (pin "2") (pinfunction "A_2") (pintype "passive"))
      (node (ref "R6") (pin "1") (pinfunction "1_1") (pintype "passive"))
    )
    (net (code "49") (name "Net-(LED6-A)") (class "Default")
      (node (ref "LED6") (pin "2") (pinfunction "A_2") (pintype "passive"))
      (node (ref "R7") (pin "1") (pinfunction "1_1") (pintype "passive"))
    )
    (net (code "50") (name "Net-(LED7-A)") (class "Default")
      (node (ref "LED7") (pin "2") (pinfunction "A_2") (pintype "passive"))
      (node (ref "R10") (pin "1") (pinfunction "1_1") (pintype "passive"))
    )
    (net (code "51") (name "Net-(LED8-A)") (class "Default")
      (node (ref "LED8") (pin "2") (pinfunction "A_2") (pintype "passive"))
      (node (ref "R12") (pin "1") (pinfunction "1_1") (pintype "passive"))
    )
    (net (code "52") (name "Net-(LED9-A)") (class "Default")
      (node (ref "LED9") (pin "2") (pinfunction "A_2") (pintype "passive"))
      (node (ref "R22") (pin "1") (pinfunction "1_1") (pintype "passive"))
    )
    (net (code "53") (name "Net-(LED10-A)") (class "Default")
      (node (ref "LED10") (pin "2") (pinfunction "A_2") (pintype "passive"))
      (node (ref "R24") (pin "1") (pinfunction "1_1") (pintype "passive"))
    )
    (net (code "54") (name "Net-(LED11-A)") (class "Default")
      (node (ref "LED11") (pin "2") (pinfunction "A_2") (pintype "passive"))
      (node (ref "R16") (pin "1") (pinfunction "1_1") (pintype "passive"))
    )
    (net (code "55") (name "Net-(LED12-A)") (class "Default")
      (node (ref "LED12") (pin "2") (pinfunction "A_2") (pintype "passive"))
      (node (ref "R17") (pin "1") (pinfunction "1_1") (pintype "passive"))
    )
    (net (code "56") (name "Net-(LED13-A)") (class "Default")
      (node (ref "LED13") (pin "2") (pinfunction "A_2") (pintype "passive"))
      (node (ref "R18") (pin "1") (pinfunction "1_1") (pintype "passive"))
    )
    (net (code "57") (name "Net-(LED14-A)") (class "Default")
      (node (ref "LED14") (pin "2") (pinfunction "A_2") (pintype "passive"))
      (node (ref "R19") (pin "1") (pinfunction "1_1") (pintype "passive"))
    )
    (net (code "58") (name "Net-(LED15-A)") (class "Default")
      (node (ref "LED15") (pin "2") (pinfunction "A_2") (pintype "passive"))
      (node (ref "R20") (pin "1") (pinfunction "1_1") (pintype "passive"))
    )
    (net (code "59") (name "Net-(LED16-A)") (class "Default")
      (node (ref "LED16") (pin "2") (pinfunction "A_2") (pintype "passive"))
      (node (ref "R21") (pin "1") (pinfunction "1_1") (pintype "passive"))
    )
    (net (code "60") (name "Net-(PS1-TRIM)") (class "Default")
      (node (ref "PS1") (pin "4") (pinfunction "TRIM_4") (pintype "passive"))
      (node (ref "VR1") (pin "2") (pinfunction "WIPER_2") (pintype "passive"))
    )
    (net (code "61") (name "Net-(PS2-TRIM)") (class "Default")
      (node (ref "PS2") (pin "4") (pinfunction "TRIM_4") (pintype "passive"))
      (node (ref "VR2") (pin "2") (pinfunction "WIPER_2") (pintype "passive"))
    )
    (net (code "62") (name "Net-(Q1-G)") (class "Default")
      (node (ref "Q1") (pin "1") (pinfunction "G_1") (pintype "passive"))
      (node (ref "R1") (pin "2") (pinfunction "2_2") (pintype "passive"))
      (node (ref "Z1") (pin "2") (pinfunction "A_2") (pintype "passive"))
    )
    (net (code "63") (name "Net-(Q2-G)") (class "Default")
      (node (ref "Q2") (pin "1") (pinfunction "G_1") (pintype "passive"))
      (node (ref "R11") (pin "2") (pinfunction "2_2") (pintype "passive"))
      (node (ref "R8") (pin "2") (pinfunction "2_2") (pintype "passive"))
    )
    (net (code "64") (name "Net-(Q3-G)") (class "Default")
      (node (ref "Q3") (pin "1") (pinfunction "G_1") (pintype "passive"))
      (node (ref "R13") (pin "2") (pinfunction "2_2") (pintype "passive"))
      (node (ref "R9") (pin "2") (pinfunction "2_2") (pintype "passive"))
    )
    (net (code "65") (name "Net-(Q4-G)") (class "Default")
      (node (ref "Q4") (pin "1") (pinfunction "G_1") (pintype "passive"))
      (node (ref "R14") (pin "2") (pinfunction "2_2") (pintype "passive"))
      (node (ref "R23") (pin "2") (pinfunction "2_2") (pintype "passive"))
    )
    (net (code "66") (name "Net-(Q5-G)") (class "Default")
      (node (ref "Q5") (pin "1") (pinfunction "G_1") (pintype "passive"))
      (node (ref "R15") (pin "2") (pinfunction "2_2") (pintype "passive"))
      (node (ref "R25") (pin "2") (pinfunction "2_2") (pintype "passive"))
    )
    (net (code "67") (name "unconnected-(C1-+_2-Pad3)") (class "Default")
      (node (ref "C1") (pin "3") (pinfunction "+_2_3") (pintype "passive+no_connect"))
    )
    (net (code "68") (name "unconnected-(C1-+_3-Pad4)") (class "Default")
      (node (ref "C1") (pin "4") (pinfunction "+_3_4") (pintype "passive+no_connect"))
    )
    (net (code "69") (name "unconnected-(C1--_2-Pad5)") (class "Default")
      (node (ref "C1") (pin "5") (pinfunction "-_2_5") (pintype "passive+no_connect"))
    )
    (net (code "70") (name "unconnected-(C1--_3-Pad6)") (class "Default")
      (node (ref "C1") (pin "6") (pinfunction "-_3_6") (pintype "passive+no_connect"))
    )
    (net (code "71") (name "unconnected-(J2-PadMP1)") (class "Default")
      (node (ref "J2") (pin "MP1") (pinfunction "MP1_MP1") (pintype "passive"))
    )
    (net (code "72") (name "unconnected-(J2-PadMP2)") (class "Default")
      (node (ref "J2") (pin "MP2") (pinfunction "MP2_MP2") (pintype "passive"))
    )
    (net (code "73") (name "unconnected-(J2-PadMP3)") (class "Default")
      (node (ref "J2") (pin "MP3") (pinfunction "MP3_MP3") (pintype "passive"))
    )
    (net (code "74") (name "unconnected-(J2-PadMP4)") (class "Default")
      (node (ref "J2") (pin "MP4") (pinfunction "MP4_MP4") (pintype "passive"))
    )
    (net (code "75") (name "unconnected-(J3-PadMP1)") (class "Default")
      (node (ref "J3") (pin "MP1") (pinfunction "MP1_MP1") (pintype "passive+no_connect"))
    )
    (net (code "76") (name "unconnected-(J3-PadMP2)") (class "Default")
      (node (ref "J3") (pin "MP2") (pinfunction "MP2_MP2") (pintype "passive+no_connect"))
    )
    (net (code "77") (name "unconnected-(J3-PadMP3)") (class "Default")
      (node (ref "J3") (pin "MP3") (pinfunction "MP3_MP3") (pintype "passive+no_connect"))
    )
    (net (code "78") (name "unconnected-(J3-PadMP4)") (class "Default")
      (node (ref "J3") (pin "MP4") (pinfunction "MP4_MP4") (pintype "passive+no_connect"))
    )
    (net (code "79") (name "unconnected-(J4-PadMP1)") (class "Default")
      (node (ref "J4") (pin "MP1") (pinfunction "MP1_MP1") (pintype "passive+no_connect"))
    )
    (net (code "80") (name "unconnected-(J4-PadMP2)") (class "Default")
      (node (ref "J4") (pin "MP2") (pinfunction "MP2_MP2") (pintype "passive+no_connect"))
    )
    (net (code "81") (name "unconnected-(J4-PadMP3)") (class "Default")
      (node (ref "J4") (pin "MP3") (pinfunction "MP3_MP3") (pintype "passive+no_connect"))
    )
    (net (code "82") (name "unconnected-(J4-PadMP4)") (class "Default")
      (node (ref "J4") (pin "MP4") (pinfunction "MP4_MP4") (pintype "passive+no_connect"))
    )
    (net (code "83") (name "unconnected-(J5-MP1-Pad1)") (class "Default")
      (node (ref "J5") (pin "1") (pinfunction "MP1_1") (pintype "passive+no_connect"))
    )
    (net (code "84") (name "unconnected-(J5-MP2-Pad2)") (class "Default")
      (node (ref "J5") (pin "2") (pinfunction "MP2_2") (pintype "passive+no_connect"))
    )
    (net (code "85") (name "unconnected-(J5-MP3-Pad3)") (class "Default")
      (node (ref "J5") (pin "3") (pinfunction "MP3_3") (pintype "passive+no_connect"))
    )
    (net (code "86") (name "unconnected-(J5-MP4-Pad4)") (class "Default")
      (node (ref "J5") (pin "4") (pinfunction "MP4_4") (pintype "passive+no_connect"))
    )
    (net (code "87") (name "unconnected-(J6-MP1-Pad1)") (class "Default")
      (node (ref "J6") (pin "1") (pinfunction "MP1_1") (pintype "passive+no_connect"))
    )
    (net (code "88") (name "unconnected-(J6-MP2-Pad2)") (class "Default")
      (node (ref "J6") (pin "2") (pinfunction "MP2_2") (pintype "passive+no_connect"))
    )
    (net (code "89") (name "unconnected-(J6-MP3-Pad3)") (class "Default")
      (node (ref "J6") (pin "3") (pinfunction "MP3_3") (pintype "passive+no_connect"))
    )
    (net (code "90") (name "unconnected-(J6-MP4-Pad4)") (class "Default")
      (node (ref "J6") (pin "4") (pinfunction "MP4_4") (pintype "passive+no_connect"))
    )
    (net (code "91") (name "unconnected-(J7-PadMP1)") (class "Default")
      (node (ref "J7") (pin "MP1") (pinfunction "MP1_MP1") (pintype "passive+no_connect"))
    )
    (net (code "92") (name "unconnected-(J7-PadMP2)") (class "Default")
      (node (ref "J7") (pin "MP2") (pinfunction "MP2_MP2") (pintype "passive+no_connect"))
    )
    (net (code "93") (name "unconnected-(J7-PadMP3)") (class "Default")
      (node (ref "J7") (pin "MP3") (pinfunction "MP3_MP3") (pintype "passive+no_connect"))
    )
    (net (code "94") (name "unconnected-(J7-PadMP4)") (class "Default")
      (node (ref "J7") (pin "MP4") (pinfunction "MP4_MP4") (pintype "passive+no_connect"))
    )
    (net (code "95") (name "unconnected-(J8-PadMP1)") (class "Default")
      (node (ref "J8") (pin "MP1") (pinfunction "MP1_MP1") (pintype "passive+no_connect"))
    )
    (net (code "96") (name "unconnected-(J8-PadMP2)") (class "Default")
      (node (ref "J8") (pin "MP2") (pinfunction "MP2_MP2") (pintype "passive+no_connect"))
    )
    (net (code "97") (name "unconnected-(J8-PadMP3)") (class "Default")
      (node (ref "J8") (pin "MP3") (pinfunction "MP3_MP3") (pintype "passive+no_connect"))
    )
    (net (code "98") (name "unconnected-(J8-PadMP4)") (class "Default")
      (node (ref "J8") (pin "MP4") (pinfunction "MP4_MP4") (pintype "passive+no_connect"))
    )
    (net (code "99") (name "unconnected-(J9-MP1-Pad1)") (class "Default")
      (node (ref "J9") (pin "1") (pinfunction "MP1_1") (pintype "passive+no_connect"))
    )
    (net (code "100") (name "unconnected-(J9-MP2-Pad2)") (class "Default")
      (node (ref "J9") (pin "2") (pinfunction "MP2_2") (pintype "passive+no_connect"))
    )
    (net (code "101") (name "unconnected-(J9-MP3-Pad3)") (class "Default")
      (node (ref "J9") (pin "3") (pinfunction "MP3_3") (pintype "passive+no_connect"))
    )
    (net (code "102") (name "unconnected-(J9-MP4-Pad4)") (class "Default")
      (node (ref "J9") (pin "4") (pinfunction "MP4_4") (pintype "passive+no_connect"))
    )
    (net (code "103") (name "unconnected-(J10-MP1-Pad1)") (class "Default")
      (node (ref "J10") (pin "1") (pinfunction "MP1_1") (pintype "passive+no_connect"))
    )
    (net (code "104") (name "unconnected-(J10-MP2-Pad2)") (class "Default")
      (node (ref "J10") (pin "2") (pinfunction "MP2_2") (pintype "passive+no_connect"))
    )
    (net (code "105") (name "unconnected-(J10-MP3-Pad3)") (class "Default")
      (node (ref "J10") (pin "3") (pinfunction "MP3_3") (pintype "passive+no_connect"))
    )
    (net (code "106") (name "unconnected-(J10-MP4-Pad4)") (class "Default")
      (node (ref "J10") (pin "4") (pinfunction "MP4_4") (pintype "passive+no_connect"))
    )
    (net (code "107") (name "unconnected-(J11-PadMP1)") (class "Default")
      (node (ref "J11") (pin "MP1") (pinfunction "MP1_MP1") (pintype "passive"))
    )
    (net (code "108") (name "unconnected-(J11-PadMP2)") (class "Default")
      (node (ref "J11") (pin "MP2") (pinfunction "MP2_MP2") (pintype "passive"))
    )
    (net (code "109") (name "unconnected-(J11-PadMP3)") (class "Default")
      (node (ref "J11") (pin "MP3") (pinfunction "MP3_MP3") (pintype "passive"))
    )
    (net (code "110") (name "unconnected-(J11-PadMP4)") (class "Default")
      (node (ref "J11") (pin "MP4") (pinfunction "MP4_MP4") (pintype "passive"))
    )
    (net (code "111") (name "unconnected-(J12-PadMP1)") (class "Default")
      (node (ref "J12") (pin "MP1") (pinfunction "MP1_MP1") (pintype "passive"))
    )
    (net (code "112") (name "unconnected-(J12-PadMP2)") (class "Default")
      (node (ref "J12") (pin "MP2") (pinfunction "MP2_MP2") (pintype "passive"))
    )
    (net (code "113") (name "unconnected-(J12-PadMP3)") (class "Default")
      (node (ref "J12") (pin "MP3") (pinfunction "MP3_MP3") (pintype "passive"))
    )
    (net (code "114") (name "unconnected-(J12-PadMP4)") (class "Default")
      (node (ref "J12") (pin "MP4") (pinfunction "MP4_MP4") (pintype "passive"))
    )
    (net (code "115") (name "unconnected-(PS1--VOUT-Pad5)") (class "Default")
      (node (ref "PS1") (pin "5") (pinfunction "-VOUT_5") (pintype "passive+no_connect"))
    )
    (net (code "116") (name "unconnected-(PS1-REMOTE_ON{slash}OFF-Pad6)") (class "Default")
      (node (ref "PS1") (pin "6") (pinfunction "REMOTE_ON/OFF_6") (pintype "passive+no_connect"))
    )
    (net (code "117") (name "unconnected-(PS2--VOUT-Pad5)") (class "Default")
      (node (ref "PS2") (pin "5") (pinfunction "-VOUT_5") (pintype "passive+no_connect"))
    )
    (net (code "118") (name "unconnected-(PS2-REMOTE_ON{slash}OFF-Pad6)") (class "Default")
      (node (ref "PS2") (pin "6") (pinfunction "REMOTE_ON/OFF_6") (pintype "passive+no_connect"))
    )
  )
)
